# Schematic.net
KiCad netlist of a schematic drawn in Altium Designer
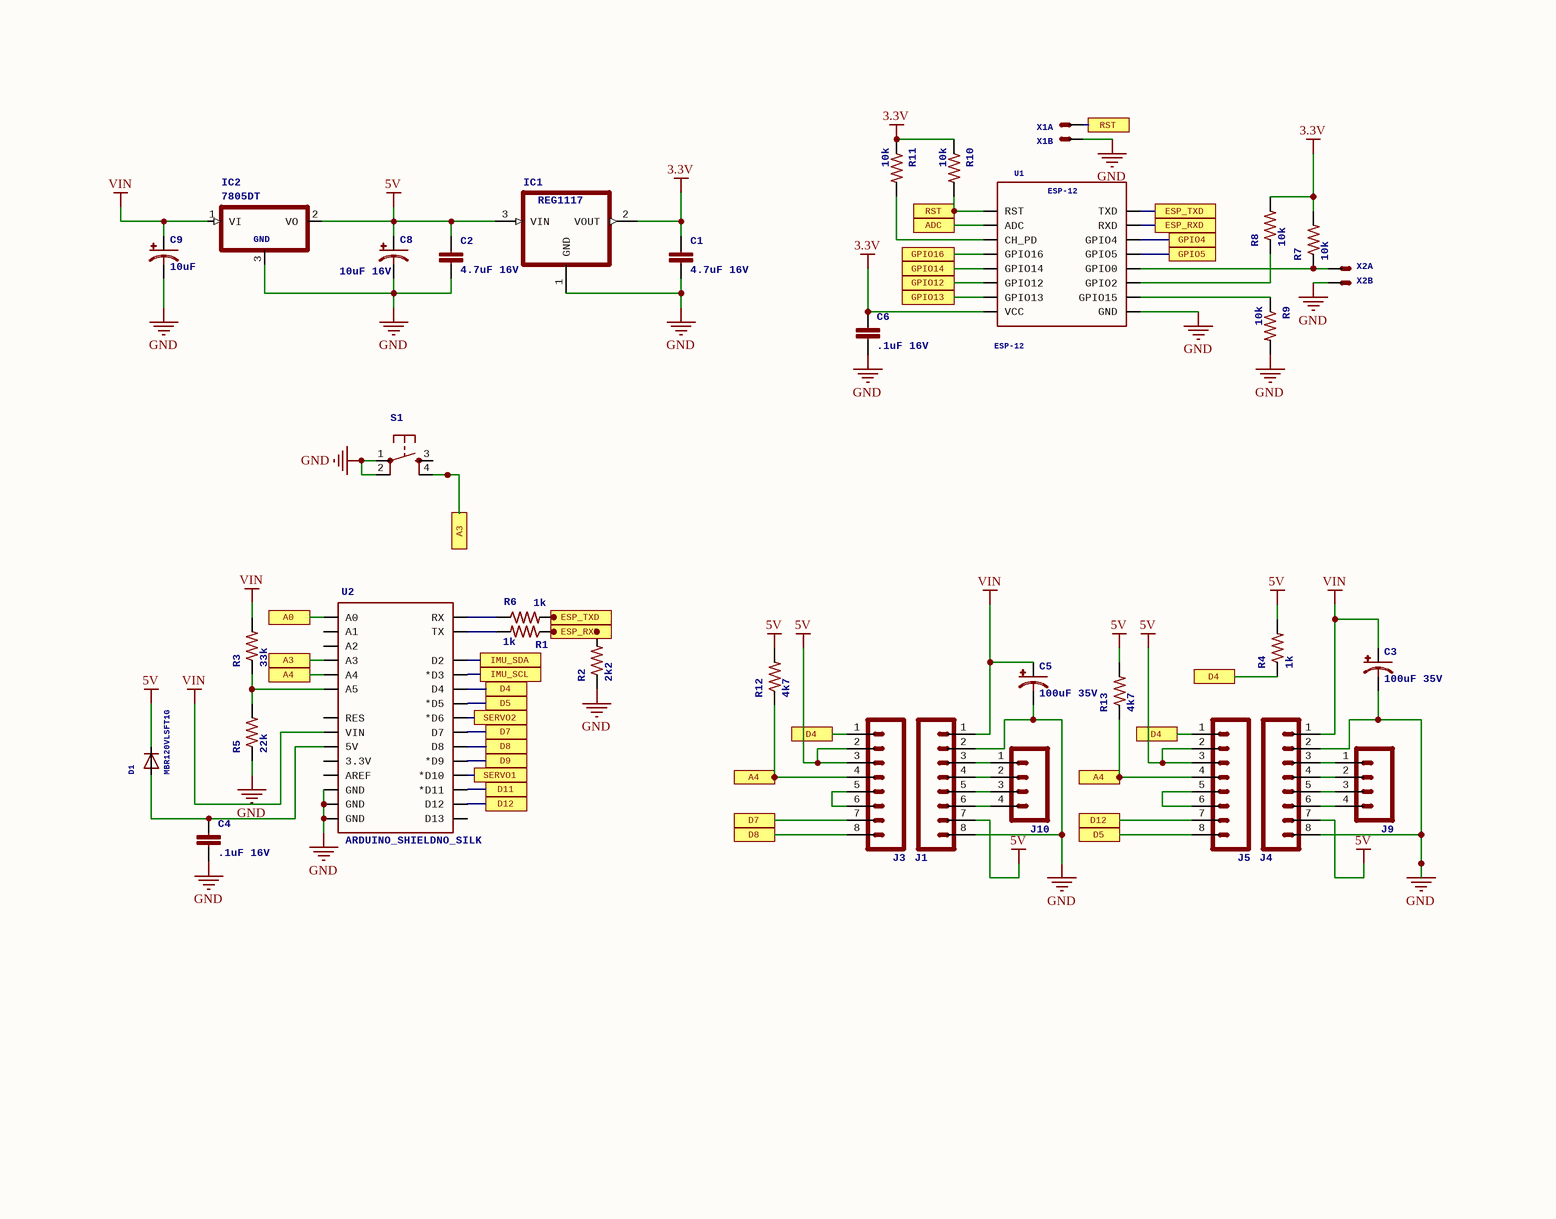
[diagram p0: Schematic.SchDoc]

(export (version "E")
  (design (tool "Eeschema 10.0.6"))
  (components
    (comp (ref "C1")
      (value "4.7uF 16V")
      (footprint "1206-CAP")
      (description "CapacitorStandard 0603 ceramic capacitor, and 0.1\" leaded capacitor.")
      (fields (field (name "LIBRARYNAME") "pixhawk2"))
      (libsource (lib "pixhawk2") (part "CAP1206"))
    )
    (comp (ref "C2")
      (value "4.7uF 16V")
      (footprint "1206-CAP")
      (description "CapacitorStandard 0603 ceramic capacitor, and 0.1\" leaded capacitor.")
      (fields (field (name "LIBRARYNAME") "pixhawk2"))
      (libsource (lib "pixhawk2") (part "CAP1206"))
    )
    (comp (ref "C3")
      (value "100uF 35V")
      (footprint "PANASONIC_D")
      (libsource (lib "SparkFun-Passives") (part "CAP_POLD"))
    )
    (comp (ref "C4")
      (value ".1uF 16V")
      (footprint "0603-CAP")
      (description "CapacitorStandard 0603 ceramic capacitor, and 0.1\" leaded capacitor.")
      (libsource (lib "SparkFun-Passives") (part "CAP0603-CAP"))
    )
    (comp (ref "C5")
      (value "100uF 35V")
      (footprint "PANASONIC_D")
      (libsource (lib "SparkFun-Passives") (part "CAP_POLD"))
    )
    (comp (ref "C6")
      (value ".1uF 16V")
      (footprint "0603-CAP")
      (description "CapacitorStandard 0603 ceramic capacitor, and 0.1\" leaded capacitor.")
      (libsource (lib "SparkFun-Passives") (part "CAP0603-CAP"))
    )
    (comp (ref "C8")
      (value "10uF 16V")
      (footprint "EIA3216")
      (libsource (lib "SparkFun-Passives") (part "CAP_POL1206"))
    )
    (comp (ref "C9")
      (value "10uF")
      (footprint "EIA3216")
      (libsource (lib "SparkFun-Passives") (part "CAP_POL1206"))
    )
    (comp (ref "D1")
      (value "MBR120VLSFT1G")
      (footprint "SOD-123")
      (libsource (lib "adafruit") (part "DIODESOD-123"))
    )
    (comp (ref "IC1")
      (value "REG1117")
      (footprint "SOT223")
      (description "800mA and 1A Low Dropout (LDO) Positive Regulator   1.8V, 2.5V, 2.85V, 3.3V, 5V, and Adj")
      (fields (field (name "LIBRARYNAME") "burr-brown"))
      (libsource (lib "burr-brown") (part "REG1117"))
    )
    (comp (ref "IC2")
      (value "7805DT")
      (footprint "TO252")
      (fields (field (name "GND") "GND"))
      (libsource (lib "linear") (part "78*DT"))
    )
    (comp (ref "J1")
      (value "PRT-11543")
      (footprint "1X08_SMD")
      (libsource (lib "SparkFun-Connectors") (part "M08SMD-STRAIGHT-FEMALE"))
    )
    (comp (ref "J3")
      (value "PRT-11543")
      (footprint "1X08_SMD")
      (libsource (lib "SparkFun-Connectors") (part "M08SMD-STRAIGHT-FEMALE"))
    )
    (comp (ref "J4")
      (value "PRT-11543")
      (footprint "1X08_SMD")
      (libsource (lib "SparkFun-Connectors") (part "M08SMD-STRAIGHT-FEMALE"))
    )
    (comp (ref "J5")
      (value "PRT-11543")
      (footprint "1X08_SMD")
      (libsource (lib "SparkFun-Connectors") (part "M08SMD-STRAIGHT-FEMALE"))
    )
    (comp (ref "J9")
      (value "M04SMD_STRAIGHT_REVERSED")
      (footprint "1X04_SMD_STRAIGHT_REVERSED")
      (libsource (lib "#mRo") (part "M04SMD_STRAIGHT_REVERSED"))
    )
    (comp (ref "J10")
      (value "M04SMD_STRAIGHT_REVERSED")
      (footprint "1X04_SMD_STRAIGHT_REVERSED")
      (libsource (lib "#mRo") (part "M04SMD_STRAIGHT_REVERSED"))
    )
    (comp (ref "R1")
      (value "1k")
      (footprint "0603-RES")
      (description "ResistorBasic schematic elements and footprints for 0603, 1206, and PTH resistors.")
      (libsource (lib "SparkFun-Passives") (part "RESISTOR0603-RES"))
    )
    (comp (ref "R2")
      (value "2k2")
      (footprint "0603-RES")
      (description "ResistorBasic schematic elements and footprints for 0603, 1206, and PTH resistors.")
      (libsource (lib "SparkFun-Passives") (part "RESISTOR0603-RES"))
    )
    (comp (ref "R3")
      (value "33k")
      (footprint "0603-RES")
      (description "ResistorBasic schematic elements and footprints for 0603, 1206, and PTH resistors.")
      (libsource (lib "SparkFun-Passives") (part "RESISTOR0603-RES"))
    )
    (comp (ref "R4")
      (value "1k")
      (footprint "0603-RES")
      (description "ResistorBasic schematic elements and footprints for 0603, 1206, and PTH resistors.")
      (libsource (lib "SparkFun-Passives") (part "RESISTOR0603-RES"))
    )
    (comp (ref "R5")
      (value "22k")
      (footprint "0603-RES")
      (description "ResistorBasic schematic elements and footprints for 0603, 1206, and PTH resistors.")
      (libsource (lib "SparkFun-Passives") (part "RESISTOR0603-RES"))
    )
    (comp (ref "R6")
      (value "1k")
      (footprint "0603-RES")
      (description "ResistorBasic schematic elements and footprints for 0603, 1206, and PTH resistors.")
      (libsource (lib "SparkFun-Passives") (part "RESISTOR0603-RES"))
    )
    (comp (ref "R7")
      (value "10k")
      (footprint "0603-RES")
      (description "ResistorBasic schematic elements and footprints for 0603, 1206, and PTH resistors.")
      (libsource (lib "SparkFun-Passives") (part "RESISTOR0603-RES"))
    )
    (comp (ref "R8")
      (value "10k")
      (footprint "0603-RES")
      (description "ResistorBasic schematic elements and footprints for 0603, 1206, and PTH resistors.")
      (libsource (lib "SparkFun-Passives") (part "RESISTOR0603-RES"))
    )
    (comp (ref "R9")
      (value "10k")
      (footprint "0603-RES")
      (description "ResistorBasic schematic elements and footprints for 0603, 1206, and PTH resistors.")
      (libsource (lib "SparkFun-Passives") (part "RESISTOR0603-RES"))
    )
    (comp (ref "R10")
      (value "10k")
      (footprint "0603-RES")
      (description "ResistorBasic schematic elements and footprints for 0603, 1206, and PTH resistors.")
      (libsource (lib "SparkFun-Passives") (part "RESISTOR0603-RES"))
    )
    (comp (ref "R11")
      (value "10k")
      (footprint "0603-RES")
      (description "ResistorBasic schematic elements and footprints for 0603, 1206, and PTH resistors.")
      (libsource (lib "SparkFun-Passives") (part "RESISTOR0603-RES"))
    )
    (comp (ref "R12")
      (value "4k7")
      (footprint "0603-RES")
      (description "ResistorBasic schematic elements and footprints for 0603, 1206, and PTH resistors.")
      (libsource (lib "SparkFun-Passives") (part "RESISTOR0603-RES"))
    )
    (comp (ref "R13")
      (value "4k7")
      (footprint "0603-RES")
      (description "ResistorBasic schematic elements and footprints for 0603, 1206, and PTH resistors.")
      (libsource (lib "SparkFun-Passives") (part "RESISTOR0603-RES"))
    )
    (comp (ref "S1")
      (value "TAC_SWITCHSMD")
      (footprint "TACTILE_SWITCH_SMD")
      (fields (field (name "LIBRARYNAME") "DIYdrones3"))
      (libsource (lib "DIYdrones3") (part "TAC_SWITCHSMD"))
    )
    (comp (ref "U1")
      (value "ESP-12")
      (footprint "ESP-12_SMD")
      (description "ESP8266 ESP-12 WIFI Module")
      (fields (field (name "ESP-12") "ESP-12"))
      (libsource (lib "#mRo") (part "ESP-12"))
    )
    (comp (ref "U2")
      (value "ARDUINO_SHIELDNO_SILK")
      (footprint "DUEMILANOVE_VIAS")
      (description "Arduino shield footprint")
      (libsource (lib "SparkFun-Boards") (part "ARDUINO_SHIELDNO_SILK"))
    )
    (comp (ref "X1")
      (value "87758-0216")
      (footprint "87758-0216")
      (libsource (lib "con-molex") (part "87758-0216"))
    )
    (comp (ref "X2")
      (value "87758-0216")
      (footprint "87758-0216")
      (libsource (lib "con-molex") (part "87758-0216"))
    )
  )
  (nets
    (net (code "1") (name "/A0") (class "Default")
      (node (ref "U2") (pin "A0") (pinfunction "A0_A0") (pintype "bidirectional"))
    )
    (net (code "2") (name "/A3") (class "Default")
      (node (ref "U2") (pin "A3") (pinfunction "A3_A3") (pintype "bidirectional"))
    )
    (net (code "3") (name "/A4") (class "Default")
      (node (ref "J3") (pin "4") (pinfunction "4_4") (pintype "passive"))
      (node (ref "J5") (pin "4") (pinfunction "4_4") (pintype "passive"))
      (node (ref "R12") (pin "1") (pinfunction "1_1") (pintype "passive"))
      (node (ref "R13") (pin "1") (pinfunction "1_1") (pintype "passive"))
      (node (ref "U2") (pin "A4") (pinfunction "A4_A4") (pintype "bidirectional"))
    )
    (net (code "4") (name "/ADC") (class "Default")
      (node (ref "U1") (pin "S2") (pinfunction "ADC_S2") (pintype "bidirectional"))
    )
    (net (code "5") (name "/D4") (class "Default")
      (node (ref "J3") (pin "1") (pinfunction "1_1") (pintype "passive"))
      (node (ref "J5") (pin "1") (pinfunction "1_1") (pintype "passive"))
      (node (ref "R4") (pin "1") (pinfunction "1_1") (pintype "passive"))
      (node (ref "U2") (pin "D4") (pinfunction "D4_D4") (pintype "bidirectional"))
    )
    (net (code "6") (name "/D5") (class "Default")
      (node (ref "J5") (pin "8") (pinfunction "8_8") (pintype "passive"))
      (node (ref "U2") (pin "D5") (pinfunction "*D5_D5") (pintype "bidirectional"))
    )
    (net (code "7") (name "/D7") (class "Default")
      (node (ref "J3") (pin "7") (pinfunction "7_7") (pintype "passive"))
      (node (ref "U2") (pin "D7") (pinfunction "D7_D7") (pintype "bidirectional"))
    )
    (net (code "8") (name "/D8") (class "Default")
      (node (ref "J3") (pin "8") (pinfunction "8_8") (pintype "passive"))
      (node (ref "U2") (pin "D8") (pinfunction "D8_D8") (pintype "bidirectional"))
    )
    (net (code "9") (name "/D9") (class "Default")
      (node (ref "U2") (pin "D9") (pinfunction "*D9_D9") (pintype "bidirectional"))
    )
    (net (code "10") (name "/D11") (class "Default")
      (node (ref "U2") (pin "D11") (pinfunction "*D11_D11") (pintype "bidirectional"))
    )
    (net (code "11") (name "/D12") (class "Default")
      (node (ref "J5") (pin "7") (pinfunction "7_7") (pintype "passive"))
      (node (ref "U2") (pin "D12") (pinfunction "D12_D12") (pintype "bidirectional"))
    )
    (net (code "12") (name "/ESP_RXD") (class "Default")
      (node (ref "U1") (pin "S15") (pinfunction "RXD_S15") (pintype "bidirectional"))
    )
    (net (code "13") (name "/ESP_TXD") (class "Default")
      (node (ref "U1") (pin "S16") (pinfunction "TXD_S16") (pintype "bidirectional"))
    )
    (net (code "14") (name "/GPIO4") (class "Default")
      (node (ref "U1") (pin "S14") (pinfunction "GPIO4_S14") (pintype "bidirectional"))
    )
    (net (code "15") (name "/GPIO5") (class "Default")
      (node (ref "U1") (pin "S13") (pinfunction "GPIO5_S13") (pintype "bidirectional"))
    )
    (net (code "16") (name "/GPIO12") (class "Default")
      (node (ref "U1") (pin "S6") (pinfunction "GPIO12_S6") (pintype "bidirectional"))
    )
    (net (code "17") (name "/GPIO13") (class "Default")
      (node (ref "U1") (pin "S7") (pinfunction "GPIO13_S7") (pintype "bidirectional"))
    )
    (net (code "18") (name "/GPIO14") (class "Default")
      (node (ref "U1") (pin "S5") (pinfunction "GPIO14_S5") (pintype "bidirectional"))
    )
    (net (code "19") (name "/GPIO16") (class "Default")
      (node (ref "U1") (pin "S4") (pinfunction "GPIO16_S4") (pintype "bidirectional"))
    )
    (net (code "20") (name "/IMU_SCL") (class "Default")
      (node (ref "U2") (pin "D3") (pinfunction "*D3_D3") (pintype "bidirectional"))
    )
    (net (code "21") (name "/IMU_SDA") (class "Default")
      (node (ref "U2") (pin "D2") (pinfunction "D2_D2") (pintype "bidirectional"))
    )
    (net (code "22") (name "/RST") (class "Default")
      (node (ref "R10") (pin "2") (pinfunction "2_2") (pintype "passive"))
      (node (ref "U1") (pin "S1") (pinfunction "RST_S1") (pintype "bidirectional"))
      (node (ref "X1") (pin "1") (pinfunction "S_1") (pintype "passive"))
    )
    (net (code "23") (name "/SERVO1") (class "Default")
      (node (ref "U2") (pin "D10") (pinfunction "*D10_D10") (pintype "bidirectional"))
    )
    (net (code "24") (name "/SERVO2") (class "Default")
      (node (ref "U2") (pin "D6") (pinfunction "*D6_D6") (pintype "bidirectional"))
    )
    (net (code "25") (name "3.3V") (class "Default")
      (node (ref "C1") (pin "P$1") (pinfunction "1_P$1") (pintype "passive"))
      (node (ref "C6") (pin "1") (pinfunction "1_1") (pintype "passive"))
      (node (ref "IC1") (pin "2") (pinfunction "VOUT_2") (pintype "output"))
      (node (ref "R10") (pin "1") (pinfunction "1_1") (pintype "passive"))
      (node (ref "R11") (pin "1") (pinfunction "1_1") (pintype "passive"))
      (node (ref "R7") (pin "2") (pinfunction "2_2") (pintype "passive"))
      (node (ref "R8") (pin "2") (pinfunction "2_2") (pintype "passive"))
      (node (ref "U1") (pin "S8") (pinfunction "VCC_S8") (pintype "bidirectional"))
    )
    (net (code "26") (name "5V") (class "Default")
      (node (ref "C2") (pin "P$1") (pinfunction "1_P$1") (pintype "passive"))
      (node (ref "C8") (pin "A") (pinfunction "+_A") (pintype "passive"))
      (node (ref "D1") (pin "C") (pinfunction "C_C") (pintype "passive"))
      (node (ref "IC1") (pin "3") (pinfunction "VIN_3") (pintype "input"))
      (node (ref "IC2") (pin "2") (pinfunction "VO_2") (pintype "passive"))
      (node (ref "J1") (pin "7") (pinfunction "7_7") (pintype "passive"))
      (node (ref "J3") (pin "2") (pinfunction "2_2") (pintype "passive"))
      (node (ref "J3") (pin "3") (pinfunction "3_3") (pintype "passive"))
      (node (ref "J4") (pin "7") (pinfunction "7_7") (pintype "passive"))
      (node (ref "J5") (pin "2") (pinfunction "2_2") (pintype "passive"))
      (node (ref "J5") (pin "3") (pinfunction "3_3") (pintype "passive"))
      (node (ref "R12") (pin "2") (pinfunction "2_2") (pintype "passive"))
      (node (ref "R13") (pin "2") (pinfunction "2_2") (pintype "passive"))
      (node (ref "R4") (pin "2") (pinfunction "2_2") (pintype "passive"))
    )
    (net (code "27") (name "GND") (class "Default")
      (node (ref "C1") (pin "P$2") (pinfunction "2_P$2") (pintype "passive"))
      (node (ref "C2") (pin "P$2") (pinfunction "2_P$2") (pintype "passive"))
      (node (ref "C3") (pin "-") (pinfunction "-_-") (pintype "passive"))
      (node (ref "C4") (pin "2") (pinfunction "2_2") (pintype "passive"))
      (node (ref "C5") (pin "-") (pinfunction "-_-") (pintype "passive"))
      (node (ref "C6") (pin "2") (pinfunction "2_2") (pintype "passive"))
      (node (ref "C8") (pin "C") (pinfunction "-_C") (pintype "passive"))
      (node (ref "C9") (pin "C") (pinfunction "-_C") (pintype "passive"))
      (node (ref "IC1") (pin "1") (pinfunction "GND_1") (pintype "power_in"))
      (node (ref "IC2") (pin "3") (pinfunction "GND_3") (pintype "passive"))
      (node (ref "J1") (pin "2") (pinfunction "2_2") (pintype "passive"))
      (node (ref "J1") (pin "8") (pinfunction "8_8") (pintype "passive"))
      (node (ref "J4") (pin "2") (pinfunction "2_2") (pintype "passive"))
      (node (ref "J4") (pin "8") (pinfunction "8_8") (pintype "passive"))
      (node (ref "R2") (pin "1") (pinfunction "1_1") (pintype "passive"))
      (node (ref "R5") (pin "1") (pinfunction "1_1") (pintype "passive"))
      (node (ref "R9") (pin "2") (pinfunction "2_2") (pintype "passive"))
      (node (ref "S1") (pin "1") (pinfunction "1_1") (pintype "passive"))
      (node (ref "S1") (pin "2") (pinfunction "2_2") (pintype "passive"))
      (node (ref "U1") (pin "S9") (pinfunction "GND_S9") (pintype "bidirectional"))
      (node (ref "U2") (pin "GND@0") (pinfunction "GND_GND@0") (pintype "bidirectional"))
      (node (ref "U2") (pin "GND@1") (pinfunction "GND_GND@1") (pintype "bidirectional"))
      (node (ref "U2") (pin "GND@2") (pinfunction "GND_GND@2") (pintype "bidirectional"))
      (node (ref "X1") (pin "2") (pinfunction "S_2") (pintype "passive"))
      (node (ref "X2") (pin "2") (pinfunction "S_2") (pintype "passive"))
    )
    (net (code "28") (name "Net-(C4-Pad1)") (class "Default")
      (node (ref "C4") (pin "1") (pinfunction "1_1") (pintype "passive"))
      (node (ref "D1") (pin "A") (pinfunction "A_A") (pintype "passive"))
      (node (ref "U2") (pin "5V") (pinfunction "5V_5V") (pintype "bidirectional"))
    )
    (net (code "29") (name "Net-(J1-Pad3)") (class "Default")
      (node (ref "J1") (pin "3") (pinfunction "3_3") (pintype "passive"))
      (node (ref "J10") (pin "1") (pinfunction "1_1") (pintype "passive"))
    )
    (net (code "30") (name "Net-(J1-Pad4)") (class "Default")
      (node (ref "J1") (pin "4") (pinfunction "4_4") (pintype "passive"))
      (node (ref "J10") (pin "2") (pinfunction "2_2") (pintype "passive"))
    )
    (net (code "31") (name "Net-(J1-Pad5)") (class "Default")
      (node (ref "J1") (pin "5") (pinfunction "5_5") (pintype "passive"))
      (node (ref "J10") (pin "3") (pinfunction "3_3") (pintype "passive"))
    )
    (net (code "32") (name "Net-(J1-Pad6)") (class "Default")
      (node (ref "J1") (pin "6") (pinfunction "6_6") (pintype "passive"))
      (node (ref "J10") (pin "4") (pinfunction "4_4") (pintype "passive"))
    )
    (net (code "33") (name "Net-(J3-Pad5)") (class "Default")
      (node (ref "J3") (pin "5") (pinfunction "5_5") (pintype "passive"))
      (node (ref "J3") (pin "6") (pinfunction "6_6") (pintype "passive"))
    )
    (net (code "34") (name "Net-(J4-Pad3)") (class "Default")
      (node (ref "J4") (pin "3") (pinfunction "3_3") (pintype "passive"))
      (node (ref "J9") (pin "1") (pinfunction "1_1") (pintype "passive"))
    )
    (net (code "35") (name "Net-(J4-Pad4)") (class "Default")
      (node (ref "J4") (pin "4") (pinfunction "4_4") (pintype "passive"))
      (node (ref "J9") (pin "2") (pinfunction "2_2") (pintype "passive"))
    )
    (net (code "36") (name "Net-(J4-Pad5)") (class "Default")
      (node (ref "J4") (pin "5") (pinfunction "5_5") (pintype "passive"))
      (node (ref "J9") (pin "3") (pinfunction "3_3") (pintype "passive"))
    )
    (net (code "37") (name "Net-(J4-Pad6)") (class "Default")
      (node (ref "J4") (pin "6") (pinfunction "6_6") (pintype "passive"))
      (node (ref "J9") (pin "4") (pinfunction "4_4") (pintype "passive"))
    )
    (net (code "38") (name "Net-(J5-Pad5)") (class "Default")
      (node (ref "J5") (pin "5") (pinfunction "5_5") (pintype "passive"))
      (node (ref "J5") (pin "6") (pinfunction "6_6") (pintype "passive"))
    )
    (net (code "39") (name "Net-(R1-Pad2)") (class "Default")
      (node (ref "R1") (pin "2") (pinfunction "2_2") (pintype "passive"))
      (node (ref "U2") (pin "TX") (pinfunction "TX_TX") (pintype "bidirectional"))
    )
    (net (code "40") (name "Net-(R3-Pad1)") (class "Default")
      (node (ref "R3") (pin "1") (pinfunction "1_1") (pintype "passive"))
      (node (ref "R5") (pin "2") (pinfunction "2_2") (pintype "passive"))
      (node (ref "U2") (pin "A5") (pinfunction "A5_A5") (pintype "bidirectional"))
    )
    (net (code "41") (name "Net-(R6-Pad1)") (class "Default")
      (node (ref "R6") (pin "1") (pinfunction "1_1") (pintype "passive"))
      (node (ref "U2") (pin "RX") (pinfunction "RX_RX") (pintype "bidirectional"))
    )
    (net (code "42") (name "Net-(U1-CH_PD)") (class "Default")
      (node (ref "R11") (pin "2") (pinfunction "2_2") (pintype "passive"))
      (node (ref "U1") (pin "S3") (pinfunction "CH_PD_S3") (pintype "bidirectional"))
    )
    (net (code "43") (name "Net-(U1-GPIO0)") (class "Default")
      (node (ref "R7") (pin "1") (pinfunction "1_1") (pintype "passive"))
      (node (ref "U1") (pin "S12") (pinfunction "GPIO0_S12") (pintype "bidirectional"))
      (node (ref "X2") (pin "1") (pinfunction "S_1") (pintype "passive"))
    )
    (net (code "44") (name "Net-(U1-GPIO2)") (class "Default")
      (node (ref "R8") (pin "1") (pinfunction "1_1") (pintype "passive"))
      (node (ref "U1") (pin "S11") (pinfunction "GPIO2_S11") (pintype "bidirectional"))
    )
    (net (code "45") (name "Net-(U1-GPIO15)") (class "Default")
      (node (ref "R9") (pin "1") (pinfunction "1_1") (pintype "passive"))
      (node (ref "U1") (pin "S10") (pinfunction "GPIO15_S10") (pintype "bidirectional"))
    )
    (net (code "46") (name "VIN") (class "Default")
      (node (ref "C3") (pin "+") (pinfunction "+_+") (pintype "passive"))
      (node (ref "C5") (pin "+") (pinfunction "+_+") (pintype "passive"))
      (node (ref "C9") (pin "A") (pinfunction "+_A") (pintype "passive"))
      (node (ref "IC2") (pin "1") (pinfunction "VI_1") (pintype "input"))
      (node (ref "J1") (pin "1") (pinfunction "1_1") (pintype "passive"))
      (node (ref "J4") (pin "1") (pinfunction "1_1") (pintype "passive"))
      (node (ref "R3") (pin "2") (pinfunction "2_2") (pintype "passive"))
      (node (ref "U2") (pin "VIN") (pinfunction "VIN_VIN") (pintype "bidirectional"))
    )
    (net (code "47") (name "unconnected-(R1-Pad1)") (class "Default")
      (node (ref "R1") (pin "1") (pinfunction "1_1") (pintype "passive"))
    )
    (net (code "48") (name "unconnected-(R2-Pad2)") (class "Default")
      (node (ref "R2") (pin "2") (pinfunction "2_2") (pintype "passive"))
    )
    (net (code "49") (name "unconnected-(R6-Pad2)") (class "Default")
      (node (ref "R6") (pin "2") (pinfunction "2_2") (pintype "passive"))
    )
    (net (code "50") (name "unconnected-(S1-Pad3)") (class "Default")
      (node (ref "S1") (pin "3") (pinfunction "3_3") (pintype "passive"))
    )
    (net (code "51") (name "unconnected-(S1-Pad4)") (class "Default")
      (node (ref "S1") (pin "4") (pinfunction "4_4") (pintype "passive"))
    )
    (net (code "52") (name "unconnected-(U2-Pad3.3V)") (class "Default")
      (node (ref "U2") (pin "3.3V") (pinfunction "3.3V_3.3V") (pintype "bidirectional"))
    )
    (net (code "53") (name "unconnected-(U2-PadA1)") (class "Default")
      (node (ref "U2") (pin "A1") (pinfunction "A1_A1") (pintype "bidirectional"))
    )
    (net (code "54") (name "unconnected-(U2-PadA2)") (class "Default")
      (node (ref "U2") (pin "A2") (pinfunction "A2_A2") (pintype "bidirectional"))
    )
    (net (code "55") (name "unconnected-(U2-PadAREF)") (class "Default")
      (node (ref "U2") (pin "AREF") (pinfunction "AREF_AREF") (pintype "bidirectional"))
    )
    (net (code "56") (name "unconnected-(U2-PadD13)") (class "Default")
      (node (ref "U2") (pin "D13") (pinfunction "D13_D13") (pintype "bidirectional"))
    )
    (net (code "57") (name "unconnected-(U2-PadRES)") (class "Default")
      (node (ref "U2") (pin "RES") (pinfunction "RES_RES") (pintype "bidirectional"))
    )
  )
)
